# mSAS_BNC_fanout.net
KiCad netlist of a schematic drawn in Altium Designer
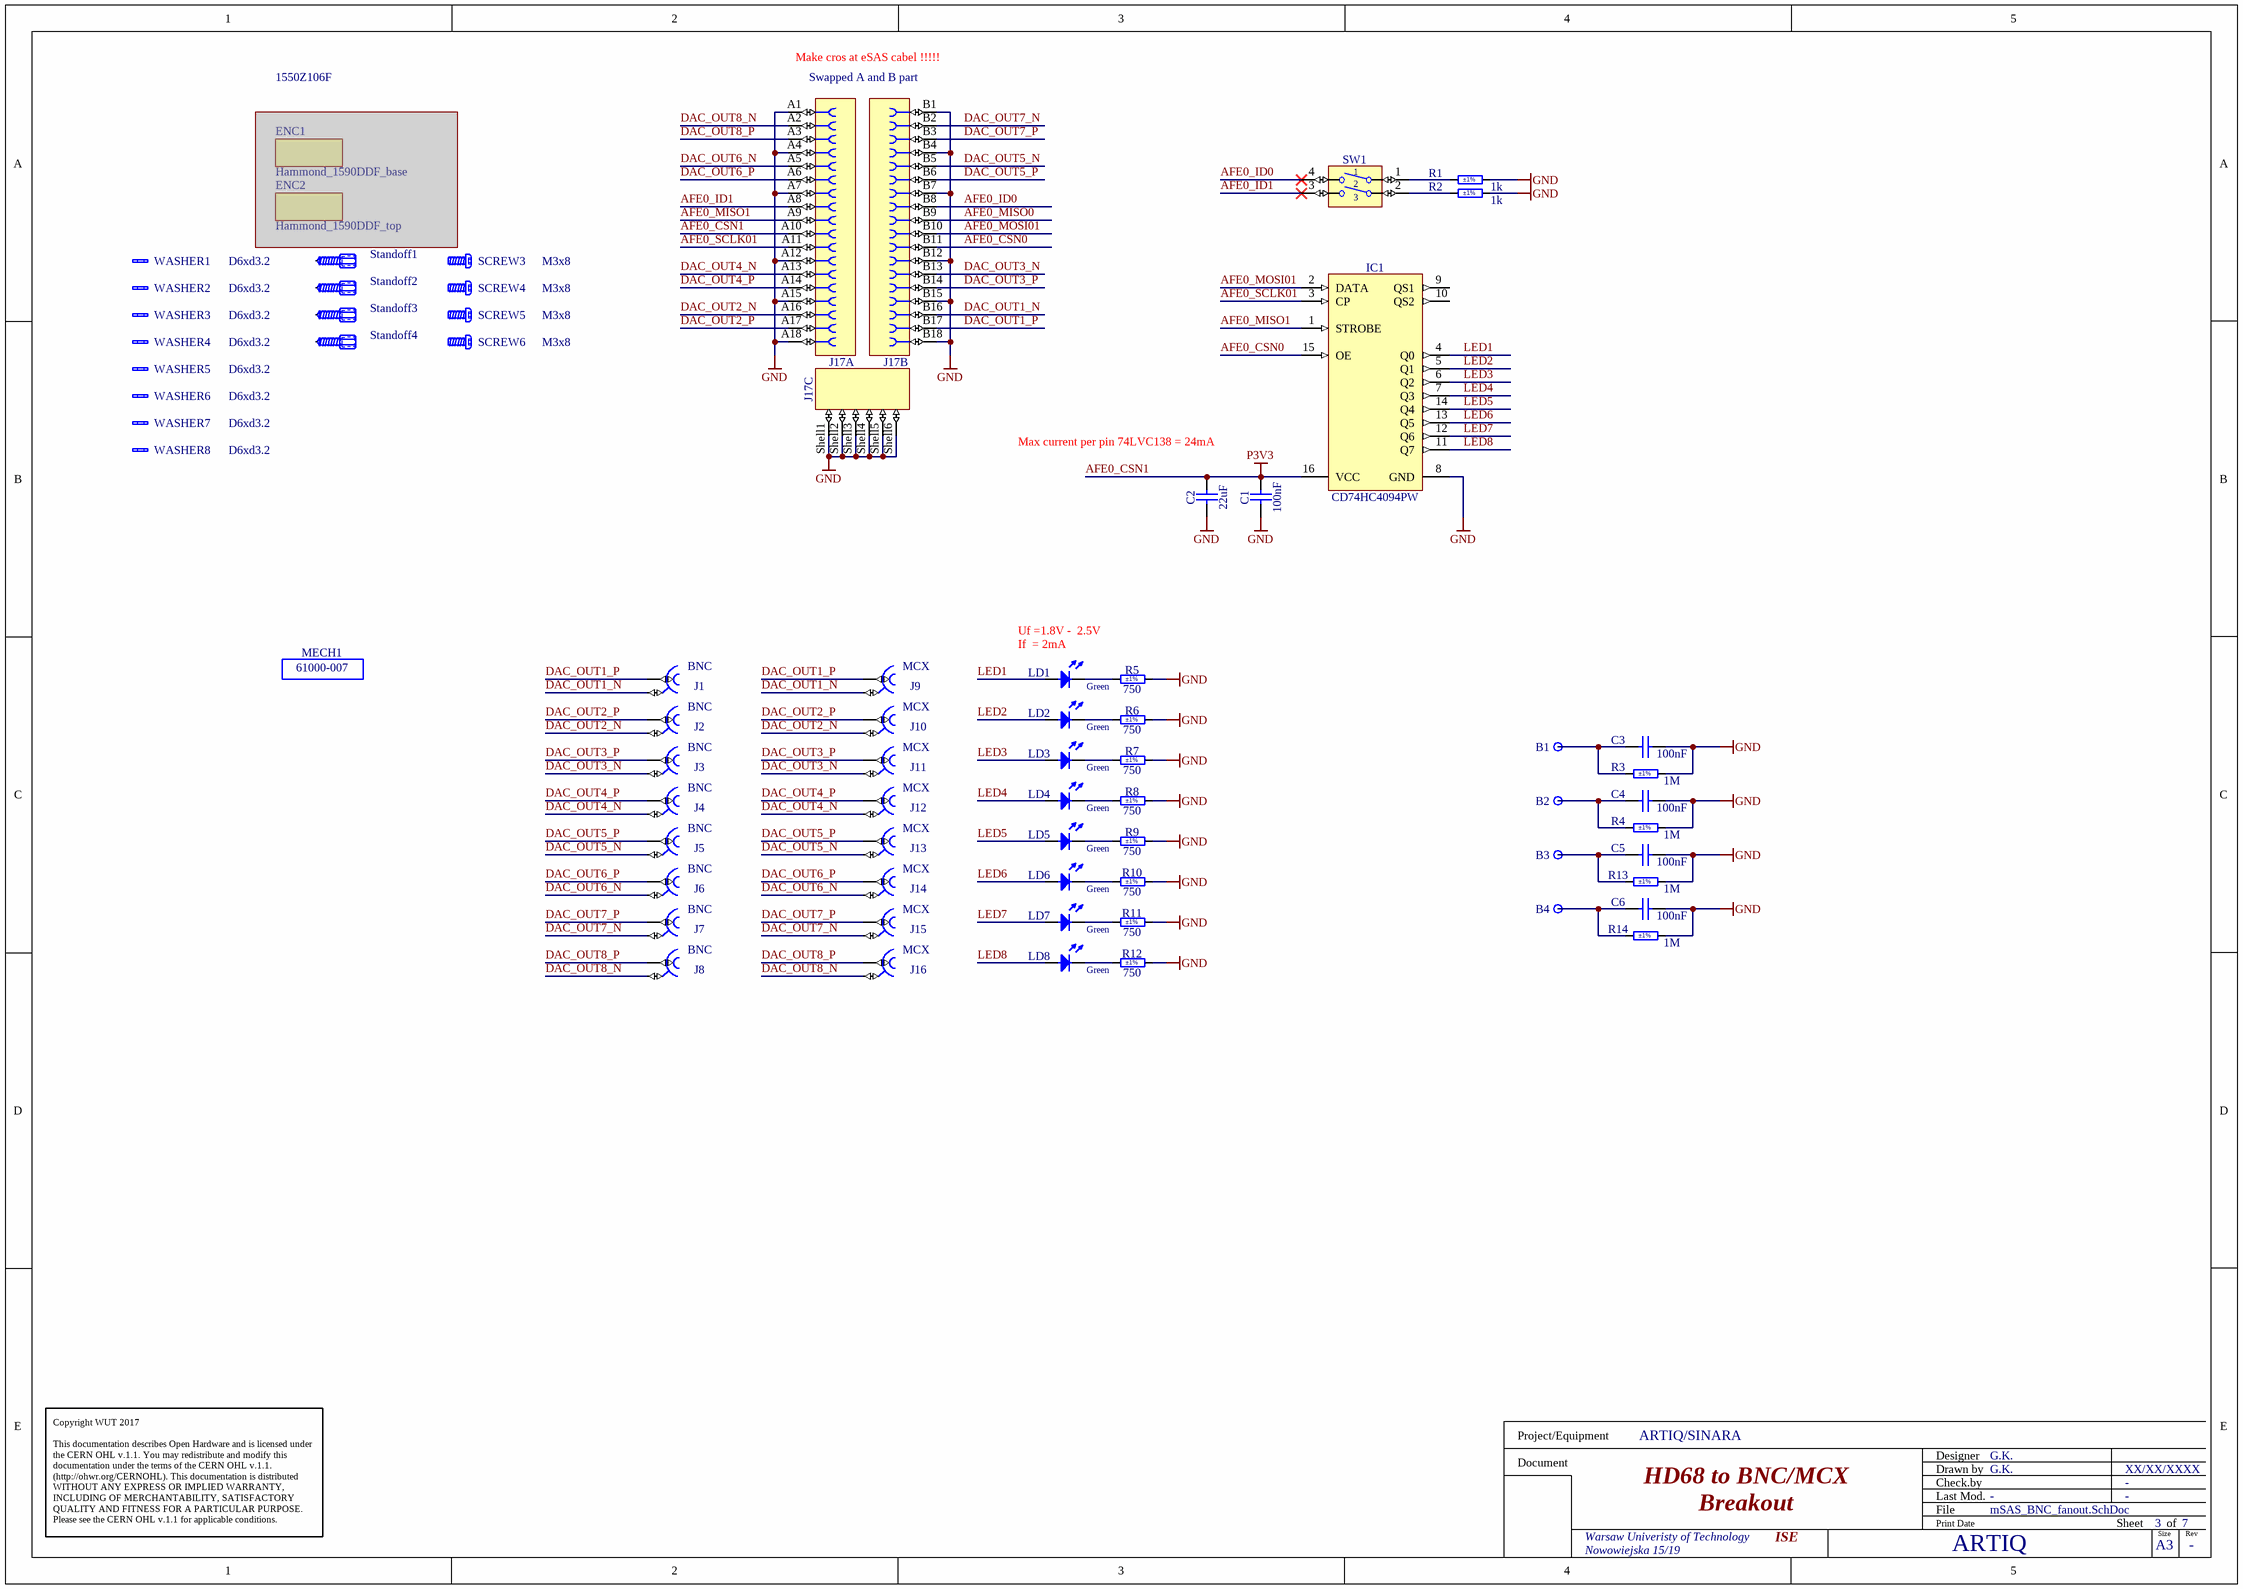
[diagram p0: mSAS_BNC_fanout.SchDoc]

(export (version "E")
  (design (tool "Eeschema 10.0.6"))
  (components
    (comp (ref "B1")
      (value "Plated Hole")
      (footprint "MTG270_500")
      (description "Single Terminal Socket")
      (fields (field (name "PART NUMBER") "PLATED_HOLE2.7_PAD5.0") (field (name "AUTHOR") "CERN DEM JMW"))
      (libsource (lib "Eletro-mechanical") (part "Single Terminal Socket"))
    )
    (comp (ref "B2")
      (value "Plated Hole")
      (footprint "MTG270_500")
      (description "Single Terminal Socket")
      (fields (field (name "PART NUMBER") "PLATED_HOLE2.7_PAD5.0") (field (name "AUTHOR") "CERN DEM JMW"))
      (libsource (lib "Eletro-mechanical") (part "Single Terminal Socket"))
    )
    (comp (ref "B3")
      (value "Plated Hole")
      (footprint "MTG270_500")
      (description "Single Terminal Socket")
      (fields (field (name "PART NUMBER") "PLATED_HOLE2.7_PAD5.0") (field (name "AUTHOR") "CERN DEM JMW"))
      (libsource (lib "Eletro-mechanical") (part "Single Terminal Socket"))
    )
    (comp (ref "B4")
      (value "Plated Hole")
      (footprint "MTG270_500")
      (description "Single Terminal Socket")
      (fields (field (name "PART NUMBER") "PLATED_HOLE2.7_PAD5.0") (field (name "AUTHOR") "CERN DEM JMW"))
      (libsource (lib "Eletro-mechanical") (part "Single Terminal Socket"))
    )
    (comp (ref "C1")
      (value "100nF")
      (footprint "CAPC1608X87N")
      (description "Non-polarised capacitor")
      (fields
        (field (name "PART NUMBER") "CC0603_100NF_50V_10%_X7R")
        (field (name "VOLTAGE") "50V")
        (field (name "AUTHOR") "CERN DEM JLC")
      )
      (libsource (lib "Capacitors") (part "Capacitor - non polarized"))
    )
    (comp (ref "C2")
      (value "22uF")
      (footprint "CAPC1608X90N")
      (description "Non-polarised capacitor")
      (fields
        (field (name "PART NUMBER") "CC0603_22UF_10V_20%_X5R")
        (field (name "VOLTAGE") "10V")
        (field (name "AUTHOR") "CERN DEM BC")
      )
      (libsource (lib "Capacitors") (part "Capacitor - non polarized"))
    )
    (comp (ref "C3")
      (value "100nF")
      (footprint "CAPC1608X90N")
      (description "Non-polarised capacitor")
      (fields
        (field (name "PART NUMBER") "CC0603_100NF_100V_10%_X7R")
        (field (name "VOLTAGE") "100V")
        (field (name "AUTHOR") "CERN DEM JLC")
      )
      (libsource (lib "Capacitors") (part "Capacitor - non polarized"))
    )
    (comp (ref "C4")
      (value "100nF")
      (footprint "CAPC1608X90N")
      (description "Non-polarised capacitor")
      (fields
        (field (name "PART NUMBER") "CC0603_100NF_100V_10%_X7R")
        (field (name "VOLTAGE") "100V")
        (field (name "AUTHOR") "CERN DEM JLC")
      )
      (libsource (lib "Capacitors") (part "Capacitor - non polarized"))
    )
    (comp (ref "C5")
      (value "100nF")
      (footprint "CAPC1608X90N")
      (description "Non-polarised capacitor")
      (fields
        (field (name "PART NUMBER") "CC0603_100NF_100V_10%_X7R")
        (field (name "VOLTAGE") "100V")
        (field (name "AUTHOR") "CERN DEM JLC")
      )
      (libsource (lib "Capacitors") (part "Capacitor - non polarized"))
    )
    (comp (ref "C6")
      (value "100nF")
      (footprint "CAPC1608X90N")
      (description "Non-polarised capacitor")
      (fields
        (field (name "PART NUMBER") "CC0603_100NF_100V_10%_X7R")
        (field (name "VOLTAGE") "100V")
        (field (name "AUTHOR") "CERN DEM JLC")
      )
      (libsource (lib "Capacitors") (part "Capacitor - non polarized"))
    )
    (comp (ref "ENC1")
      (value "Hammond_1590DDF_base")
      (footprint "1590DDF_base")
      (description "Hammond 1590DDF enclosure base part")
      (libsource (lib "Mechanical") (part "Hammond_1590DDF_base"))
    )
    (comp (ref "ENC2")
      (value "Hammond_1590DDF_top")
      (footprint "1590D-DD-E_LID_custom")
      (description "Hammond 1590DDF enclosure lid with custom cutouts")
      (libsource (lib "Mechanical") (part "Hammond_1590DDF_top_custom"))
    )
    (comp (ref "IC1")
      (value "CD74HC4094PW")
      (footprint "SOP65P640X120-16N")
      (description "High−Speed CMOS Logic, 8−Stage Shift and Store Bus Register, Three−State")
      (fields (field (name "MANUFACTURER") "TEXAS INSTRUMENTS") (field (name "AUTHOR") "CERN DEM MR"))
      (libsource (lib "ICs And Semiconductors") (part "744094"))
    )
    (comp (ref "J1")
      (value "BNC")
      (footprint "TYCO_5-1634506-1")
      (fields
        (field (name "PART NUMBER") "TYCO_5-1634506-1")
        (field (name "MANUFACTURER") "TYCO ELECTRONICS")
        (field (name "MANUFACTURER PART NUMBER") "5-1634506-1")
        (field (name "AUTHOR") "CERN DEM JLC")
      )
      (libsource (lib "Connectors") (part "Coax_1Female_1Shield"))
    )
    (comp (ref "J2")
      (value "BNC")
      (footprint "TYCO_5-1634506-1")
      (fields
        (field (name "PART NUMBER") "TYCO_5-1634506-1")
        (field (name "MANUFACTURER") "TYCO ELECTRONICS")
        (field (name "MANUFACTURER PART NUMBER") "5-1634506-1")
        (field (name "AUTHOR") "CERN DEM JLC")
      )
      (libsource (lib "Connectors") (part "Coax_1Female_1Shield"))
    )
    (comp (ref "J3")
      (value "BNC")
      (footprint "TYCO_5-1634506-1")
      (fields
        (field (name "PART NUMBER") "TYCO_5-1634506-1")
        (field (name "MANUFACTURER") "TYCO ELECTRONICS")
        (field (name "MANUFACTURER PART NUMBER") "5-1634506-1")
        (field (name "AUTHOR") "CERN DEM JLC")
      )
      (libsource (lib "Connectors") (part "Coax_1Female_1Shield"))
    )
    (comp (ref "J4")
      (value "BNC")
      (footprint "TYCO_5-1634506-1")
      (fields
        (field (name "PART NUMBER") "TYCO_5-1634506-1")
        (field (name "MANUFACTURER") "TYCO ELECTRONICS")
        (field (name "MANUFACTURER PART NUMBER") "5-1634506-1")
        (field (name "AUTHOR") "CERN DEM JLC")
      )
      (libsource (lib "Connectors") (part "Coax_1Female_1Shield"))
    )
    (comp (ref "J5")
      (value "BNC")
      (footprint "TYCO_5-1634506-1")
      (fields
        (field (name "PART NUMBER") "TYCO_5-1634506-1")
        (field (name "MANUFACTURER") "TYCO ELECTRONICS")
        (field (name "MANUFACTURER PART NUMBER") "5-1634506-1")
        (field (name "AUTHOR") "CERN DEM JLC")
      )
      (libsource (lib "Connectors") (part "Coax_1Female_1Shield"))
    )
    (comp (ref "J6")
      (value "BNC")
      (footprint "TYCO_5-1634506-1")
      (fields
        (field (name "PART NUMBER") "TYCO_5-1634506-1")
        (field (name "MANUFACTURER") "TYCO ELECTRONICS")
        (field (name "MANUFACTURER PART NUMBER") "5-1634506-1")
        (field (name "AUTHOR") "CERN DEM JLC")
      )
      (libsource (lib "Connectors") (part "Coax_1Female_1Shield"))
    )
    (comp (ref "J7")
      (value "BNC")
      (footprint "TYCO_5-1634506-1")
      (fields
        (field (name "PART NUMBER") "TYCO_5-1634506-1")
        (field (name "MANUFACTURER") "TYCO ELECTRONICS")
        (field (name "MANUFACTURER PART NUMBER") "5-1634506-1")
        (field (name "AUTHOR") "CERN DEM JLC")
      )
      (libsource (lib "Connectors") (part "Coax_1Female_1Shield"))
    )
    (comp (ref "J8")
      (value "BNC")
      (footprint "TYCO_5-1634506-1")
      (fields
        (field (name "PART NUMBER") "TYCO_5-1634506-1")
        (field (name "MANUFACTURER") "TYCO ELECTRONICS")
        (field (name "MANUFACTURER PART NUMBER") "5-1634506-1")
        (field (name "AUTHOR") "CERN DEM JLC")
      )
      (libsource (lib "Connectors") (part "Coax_1Female_1Shield"))
    )
    (comp (ref "J9")
      (value "MCX")
      (footprint "AMPHENOL_919-109J-51PX")
      (fields
        (field (name "PART NUMBER") "AMPHENOL_919-109J-51PX")
        (field (name "MANUFACTURER") "AMPHENOL")
        (field (name "MANUFACTURER PART NUMBER") "919-109J-51PX (MCX6251B1-3GT30G-50)")
        (field (name "AUTHOR") "CERN DEM BC")
      )
      (libsource (lib "Connectors") (part "Coax_1Female_1Shield"))
    )
    (comp (ref "J10")
      (value "MCX")
      (footprint "AMPHENOL_919-109J-51PX")
      (fields
        (field (name "PART NUMBER") "AMPHENOL_919-109J-51PX")
        (field (name "MANUFACTURER") "AMPHENOL")
        (field (name "MANUFACTURER PART NUMBER") "919-109J-51PX (MCX6251B1-3GT30G-50)")
        (field (name "AUTHOR") "CERN DEM BC")
      )
      (libsource (lib "Connectors") (part "Coax_1Female_1Shield"))
    )
    (comp (ref "J11")
      (value "MCX")
      (footprint "AMPHENOL_919-109J-51PX")
      (fields
        (field (name "PART NUMBER") "AMPHENOL_919-109J-51PX")
        (field (name "MANUFACTURER") "AMPHENOL")
        (field (name "MANUFACTURER PART NUMBER") "919-109J-51PX (MCX6251B1-3GT30G-50)")
        (field (name "AUTHOR") "CERN DEM BC")
      )
      (libsource (lib "Connectors") (part "Coax_1Female_1Shield"))
    )
    (comp (ref "J12")
      (value "MCX")
      (footprint "AMPHENOL_919-109J-51PX")
      (fields
        (field (name "PART NUMBER") "AMPHENOL_919-109J-51PX")
        (field (name "MANUFACTURER") "AMPHENOL")
        (field (name "MANUFACTURER PART NUMBER") "919-109J-51PX (MCX6251B1-3GT30G-50)")
        (field (name "AUTHOR") "CERN DEM BC")
      )
      (libsource (lib "Connectors") (part "Coax_1Female_1Shield"))
    )
    (comp (ref "J13")
      (value "MCX")
      (footprint "AMPHENOL_919-109J-51PX")
      (fields
        (field (name "PART NUMBER") "AMPHENOL_919-109J-51PX")
        (field (name "MANUFACTURER") "AMPHENOL")
        (field (name "MANUFACTURER PART NUMBER") "919-109J-51PX (MCX6251B1-3GT30G-50)")
        (field (name "AUTHOR") "CERN DEM BC")
      )
      (libsource (lib "Connectors") (part "Coax_1Female_1Shield"))
    )
    (comp (ref "J14")
      (value "MCX")
      (footprint "AMPHENOL_919-109J-51PX")
      (fields
        (field (name "PART NUMBER") "AMPHENOL_919-109J-51PX")
        (field (name "MANUFACTURER") "AMPHENOL")
        (field (name "MANUFACTURER PART NUMBER") "919-109J-51PX (MCX6251B1-3GT30G-50)")
        (field (name "AUTHOR") "CERN DEM BC")
      )
      (libsource (lib "Connectors") (part "Coax_1Female_1Shield"))
    )
    (comp (ref "J15")
      (value "MCX")
      (footprint "AMPHENOL_919-109J-51PX")
      (fields
        (field (name "PART NUMBER") "AMPHENOL_919-109J-51PX")
        (field (name "MANUFACTURER") "AMPHENOL")
        (field (name "MANUFACTURER PART NUMBER") "919-109J-51PX (MCX6251B1-3GT30G-50)")
        (field (name "AUTHOR") "CERN DEM BC")
      )
      (libsource (lib "Connectors") (part "Coax_1Female_1Shield"))
    )
    (comp (ref "J16")
      (value "MCX")
      (footprint "AMPHENOL_919-109J-51PX")
      (fields
        (field (name "PART NUMBER") "AMPHENOL_919-109J-51PX")
        (field (name "MANUFACTURER") "AMPHENOL")
        (field (name "MANUFACTURER PART NUMBER") "919-109J-51PX (MCX6251B1-3GT30G-50)")
        (field (name "AUTHOR") "CERN DEM BC")
      )
      (libsource (lib "Connectors") (part "Coax_1Female_1Shield"))
    )
    (comp (ref "J17")
      (value "iPass™")
      (footprint "MOLEX_75783-0107")
      (fields
        (field (name "PART NUMBER") "MOLEX 75783-0107 / 75783-0136")
        (field (name "MANUFACTURER") "MOLEX")
        (field (name "MANUFACTURER PART NUMBER") "75783-0107 / 75783-0136")
        (field (name "AUTHOR") "CERN DEM JLC")
      )
      (libsource (lib "") (part "MOLEX_75783-0107_1"))
    )
    (comp (ref "LD1")
      (value "Green")
      (footprint "LED_KINGBRIGHT_KP-1608CGCK")
      (description "LED Green 1C 2A")
      (fields
        (field (name "PART NUMBER") "LED_KINGBRIGHT_KP-1608CGCK")
        (field (name "MANUFACTURER") "KINGBRIGHT")
        (field (name "AUTHOR") "CERN DEM HF")
      )
      (libsource (lib "ICs And Semiconductors") (part "LED Green 1C 2A"))
    )
    (comp (ref "LD2")
      (value "Green")
      (footprint "LED_KINGBRIGHT_KP-1608CGCK")
      (description "LED Green 1C 2A")
      (fields
        (field (name "PART NUMBER") "LED_KINGBRIGHT_KP-1608CGCK")
        (field (name "MANUFACTURER") "KINGBRIGHT")
        (field (name "AUTHOR") "CERN DEM HF")
      )
      (libsource (lib "ICs And Semiconductors") (part "LED Green 1C 2A"))
    )
    (comp (ref "LD3")
      (value "Green")
      (footprint "LED_KINGBRIGHT_KP-1608CGCK")
      (description "LED Green 1C 2A")
      (fields
        (field (name "PART NUMBER") "LED_KINGBRIGHT_KP-1608CGCK")
        (field (name "MANUFACTURER") "KINGBRIGHT")
        (field (name "AUTHOR") "CERN DEM HF")
      )
      (libsource (lib "ICs And Semiconductors") (part "LED Green 1C 2A"))
    )
    (comp (ref "LD4")
      (value "Green")
      (footprint "LED_KINGBRIGHT_KP-1608CGCK")
      (description "LED Green 1C 2A")
      (fields
        (field (name "PART NUMBER") "LED_KINGBRIGHT_KP-1608CGCK")
        (field (name "MANUFACTURER") "KINGBRIGHT")
        (field (name "AUTHOR") "CERN DEM HF")
      )
      (libsource (lib "ICs And Semiconductors") (part "LED Green 1C 2A"))
    )
    (comp (ref "LD5")
      (value "Green")
      (footprint "LED_KINGBRIGHT_KP-1608CGCK")
      (description "LED Green 1C 2A")
      (fields
        (field (name "PART NUMBER") "LED_KINGBRIGHT_KP-1608CGCK")
        (field (name "MANUFACTURER") "KINGBRIGHT")
        (field (name "AUTHOR") "CERN DEM HF")
      )
      (libsource (lib "ICs And Semiconductors") (part "LED Green 1C 2A"))
    )
    (comp (ref "LD6")
      (value "Green")
      (footprint "LED_KINGBRIGHT_KP-1608CGCK")
      (description "LED Green 1C 2A")
      (fields
        (field (name "PART NUMBER") "LED_KINGBRIGHT_KP-1608CGCK")
        (field (name "MANUFACTURER") "KINGBRIGHT")
        (field (name "AUTHOR") "CERN DEM HF")
      )
      (libsource (lib "ICs And Semiconductors") (part "LED Green 1C 2A"))
    )
    (comp (ref "LD7")
      (value "Green")
      (footprint "LED_KINGBRIGHT_KP-1608CGCK")
      (description "LED Green 1C 2A")
      (fields
        (field (name "PART NUMBER") "LED_KINGBRIGHT_KP-1608CGCK")
        (field (name "MANUFACTURER") "KINGBRIGHT")
        (field (name "AUTHOR") "CERN DEM HF")
      )
      (libsource (lib "ICs And Semiconductors") (part "LED Green 1C 2A"))
    )
    (comp (ref "LD8")
      (value "Green")
      (footprint "LED_KINGBRIGHT_KP-1608CGCK")
      (description "LED Green 1C 2A")
      (fields
        (field (name "PART NUMBER") "LED_KINGBRIGHT_KP-1608CGCK")
        (field (name "MANUFACTURER") "KINGBRIGHT")
        (field (name "AUTHOR") "CERN DEM HF")
      )
      (libsource (lib "ICs And Semiconductors") (part "LED Green 1C 2A"))
    )
    (comp (ref "MECH1")
      (value "61000-007")
      (footprint "GENERIC_MECH")
      (description "PCB Solder Side Cover, 3 U, 100 mm x 160 mm, 55°C Schroff insulating plate")
      (fields (field (name "MANUFACTURER") "Schroff") (field (name "AUTHOR") "GK"))
      (libsource (lib "Mechanical") (part "Generic_mechanical"))
    )
    (comp (ref "R1")
      (value "1k")
      (footprint "RESC1608X55N")
      (description "Resistor - 1%")
      (fields
        (field (name "TOLERANCE") "±1%")
        (field (name "PART NUMBER") "R0603_1K_1%_0.1W_100PPM")
        (field (name "POWER") "0.1W")
        (field (name "AUTHOR") "CERN DEM JLC")
      )
      (libsource (lib "Resistors") (part "Resistor - 1%"))
    )
    (comp (ref "R2")
      (value "1k")
      (footprint "RESC1608X55N")
      (description "Resistor - 1%")
      (fields
        (field (name "TOLERANCE") "±1%")
        (field (name "PART NUMBER") "R0603_1K_1%_0.1W_100PPM")
        (field (name "POWER") "0.1W")
        (field (name "AUTHOR") "CERN DEM JLC")
      )
      (libsource (lib "Resistors") (part "Resistor - 1%"))
    )
    (comp (ref "R3")
      (value "1M")
      (footprint "RESC1608X55N")
      (description "Resistor - 1%")
      (fields
        (field (name "TOLERANCE") "±1%")
        (field (name "PART NUMBER") "R0603_1M_1%_0.1W_100PPM")
        (field (name "POWER") "0.1W")
        (field (name "AUTHOR") "CERN DEM JLC")
      )
      (libsource (lib "Resistors") (part "Resistor - 1%"))
    )
    (comp (ref "R4")
      (value "1M")
      (footprint "RESC1608X55N")
      (description "Resistor - 1%")
      (fields
        (field (name "TOLERANCE") "±1%")
        (field (name "PART NUMBER") "R0603_1M_1%_0.1W_100PPM")
        (field (name "POWER") "0.1W")
        (field (name "AUTHOR") "CERN DEM JLC")
      )
      (libsource (lib "Resistors") (part "Resistor - 1%"))
    )
    (comp (ref "R5")
      (value "750")
      (footprint "RESC1608X55N")
      (description "Resistor - 1%")
      (fields
        (field (name "TOLERANCE") "±1%")
        (field (name "PART NUMBER") "R0603_750R_1%_0.1W_100PPM")
        (field (name "POWER") "0.1W")
        (field (name "AUTHOR") "CERN DEM JLC")
      )
      (libsource (lib "Resistors") (part "Resistor - 1%"))
    )
    (comp (ref "R6")
      (value "750")
      (footprint "RESC1608X55N")
      (description "Resistor - 1%")
      (fields
        (field (name "TOLERANCE") "±1%")
        (field (name "PART NUMBER") "R0603_750R_1%_0.1W_100PPM")
        (field (name "POWER") "0.1W")
        (field (name "AUTHOR") "CERN DEM JLC")
      )
      (libsource (lib "Resistors") (part "Resistor - 1%"))
    )
    (comp (ref "R7")
      (value "750")
      (footprint "RESC1608X55N")
      (description "Resistor - 1%")
      (fields
        (field (name "TOLERANCE") "±1%")
        (field (name "PART NUMBER") "R0603_750R_1%_0.1W_100PPM")
        (field (name "POWER") "0.1W")
        (field (name "AUTHOR") "CERN DEM JLC")
      )
      (libsource (lib "Resistors") (part "Resistor - 1%"))
    )
    (comp (ref "R8")
      (value "750")
      (footprint "RESC1608X55N")
      (description "Resistor - 1%")
      (fields
        (field (name "TOLERANCE") "±1%")
        (field (name "PART NUMBER") "R0603_750R_1%_0.1W_100PPM")
        (field (name "POWER") "0.1W")
        (field (name "AUTHOR") "CERN DEM JLC")
      )
      (libsource (lib "Resistors") (part "Resistor - 1%"))
    )
    (comp (ref "R9")
      (value "750")
      (footprint "RESC1608X55N")
      (description "Resistor - 1%")
      (fields
        (field (name "TOLERANCE") "±1%")
        (field (name "PART NUMBER") "R0603_750R_1%_0.1W_100PPM")
        (field (name "POWER") "0.1W")
        (field (name "AUTHOR") "CERN DEM JLC")
      )
      (libsource (lib "Resistors") (part "Resistor - 1%"))
    )
    (comp (ref "R10")
      (value "750")
      (footprint "RESC1608X55N")
      (description "Resistor - 1%")
      (fields
        (field (name "TOLERANCE") "±1%")
        (field (name "PART NUMBER") "R0603_750R_1%_0.1W_100PPM")
        (field (name "POWER") "0.1W")
        (field (name "AUTHOR") "CERN DEM JLC")
      )
      (libsource (lib "Resistors") (part "Resistor - 1%"))
    )
    (comp (ref "R11")
      (value "750")
      (footprint "RESC1608X55N")
      (description "Resistor - 1%")
      (fields
        (field (name "TOLERANCE") "±1%")
        (field (name "PART NUMBER") "R0603_750R_1%_0.1W_100PPM")
        (field (name "POWER") "0.1W")
        (field (name "AUTHOR") "CERN DEM JLC")
      )
      (libsource (lib "Resistors") (part "Resistor - 1%"))
    )
    (comp (ref "R12")
      (value "750")
      (footprint "RESC1608X55N")
      (description "Resistor - 1%")
      (fields
        (field (name "TOLERANCE") "±1%")
        (field (name "PART NUMBER") "R0603_750R_1%_0.1W_100PPM")
        (field (name "POWER") "0.1W")
        (field (name "AUTHOR") "CERN DEM JLC")
      )
      (libsource (lib "Resistors") (part "Resistor - 1%"))
    )
    (comp (ref "R13")
      (value "1M")
      (footprint "RESC1608X55N")
      (description "Resistor - 1%")
      (fields
        (field (name "TOLERANCE") "±1%")
        (field (name "PART NUMBER") "R0603_1M_1%_0.1W_100PPM")
        (field (name "POWER") "0.1W")
        (field (name "AUTHOR") "CERN DEM JLC")
      )
      (libsource (lib "Resistors") (part "Resistor - 1%"))
    )
    (comp (ref "R14")
      (value "1M")
      (footprint "RESC1608X55N")
      (description "Resistor - 1%")
      (fields
        (field (name "TOLERANCE") "±1%")
        (field (name "PART NUMBER") "R0603_1M_1%_0.1W_100PPM")
        (field (name "POWER") "0.1W")
        (field (name "AUTHOR") "CERN DEM JLC")
      )
      (libsource (lib "Resistors") (part "Resistor - 1%"))
    )
    (comp (ref "SCREW3")
      (value "M3x8")
      (footprint "BOSSARD_BN5687-3061606_h")
      (description "Screw")
      (fields
        (field (name "PART NUMBER") "BOSSARD_BN5687-3061606_h")
        (field (name "MANUFACTURER") "BOSSARD")
        (field (name "AUTHOR") "CERN DEM JLC")
      )
      (libsource (lib "Eletro-mechanical") (part "Screw"))
    )
    (comp (ref "SCREW4")
      (value "M3x8")
      (footprint "BOSSARD_BN5687-3061606_h")
      (description "Screw")
      (fields
        (field (name "PART NUMBER") "BOSSARD_BN5687-3061606_h")
        (field (name "MANUFACTURER") "BOSSARD")
        (field (name "AUTHOR") "CERN DEM JLC")
      )
      (libsource (lib "Eletro-mechanical") (part "Screw"))
    )
    (comp (ref "SCREW5")
      (value "M3x8")
      (footprint "BOSSARD_BN5687-3061606_h")
      (description "Screw")
      (fields
        (field (name "PART NUMBER") "BOSSARD_BN5687-3061606_h")
        (field (name "MANUFACTURER") "BOSSARD")
        (field (name "AUTHOR") "CERN DEM JLC")
      )
      (libsource (lib "Eletro-mechanical") (part "Screw"))
    )
    (comp (ref "SCREW6")
      (value "M3x8")
      (footprint "BOSSARD_BN5687-3061606_h")
      (description "Screw")
      (fields
        (field (name "PART NUMBER") "BOSSARD_BN5687-3061606_h")
        (field (name "MANUFACTURER") "BOSSARD")
        (field (name "AUTHOR") "CERN DEM JLC")
      )
      (libsource (lib "Eletro-mechanical") (part "Screw"))
    )
    (comp (ref "Standoff1")
      (value "~")
      (footprint "ETTINGER_005.13.103")
      (description "Standoff Male-Female")
      (fields
        (field (name "PART NUMBER") "ETTINGER_005.13.103")
        (field (name "MANUFACTURER") "ETTINGER")
        (field (name "AUTHOR") "CERN DEM HF")
      )
      (libsource (lib "Eletro-mechanical") (part "Standoff Male-Female"))
    )
    (comp (ref "Standoff2")
      (value "~")
      (footprint "ETTINGER_005.13.103")
      (description "Standoff Male-Female")
      (fields
        (field (name "PART NUMBER") "ETTINGER_005.13.103")
        (field (name "MANUFACTURER") "ETTINGER")
        (field (name "AUTHOR") "CERN DEM HF")
      )
      (libsource (lib "Eletro-mechanical") (part "Standoff Male-Female"))
    )
    (comp (ref "Standoff3")
      (value "~")
      (footprint "ETTINGER_005.13.103")
      (description "Standoff Male-Female")
      (fields
        (field (name "PART NUMBER") "ETTINGER_005.13.103")
        (field (name "MANUFACTURER") "ETTINGER")
        (field (name "AUTHOR") "CERN DEM HF")
      )
      (libsource (lib "Eletro-mechanical") (part "Standoff Male-Female"))
    )
    (comp (ref "Standoff4")
      (value "~")
      (footprint "ETTINGER_005.13.103")
      (description "Standoff Male-Female")
      (fields
        (field (name "PART NUMBER") "ETTINGER_005.13.103")
        (field (name "MANUFACTURER") "ETTINGER")
        (field (name "AUTHOR") "CERN DEM HF")
      )
      (libsource (lib "Eletro-mechanical") (part "Standoff Male-Female"))
    )
    (comp (ref "SW1")
      (value "Switch")
      (footprint "SW_OMRON_A6DR-2101")
      (description "2 Ways SPST DIP Switch")
      (fields (field (name "PART NUMBER") "SW_OMRON_A6FR-2101") (field (name "MANUFACTURER") "OMRON"))
      (libsource (lib "eSAS_BNC_fanout") (part "SW_OMRON_A6DR-2101"))
    )
    (comp (ref "WASHER1")
      (value "D6xd3.2")
      (footprint "BOSSARD_BN83728-8243964_v")
      (description "Washer")
      (fields
        (field (name "PART NUMBER") "BOSSARD_BN83728-8243964_v")
        (field (name "MANUFACTURER") "BOSSARD")
        (field (name "AUTHOR") "CERN DEM JLC")
      )
      (libsource (lib "Eletro-mechanical") (part "Washer"))
    )
    (comp (ref "WASHER2")
      (value "D6xd3.2")
      (footprint "BOSSARD_BN83728-8243964_v")
      (description "Washer")
      (fields
        (field (name "PART NUMBER") "BOSSARD_BN83728-8243964_v")
        (field (name "MANUFACTURER") "BOSSARD")
        (field (name "AUTHOR") "CERN DEM JLC")
      )
      (libsource (lib "Eletro-mechanical") (part "Washer"))
    )
    (comp (ref "WASHER3")
      (value "D6xd3.2")
      (footprint "BOSSARD_BN83728-8243964_v")
      (description "Washer")
      (fields
        (field (name "PART NUMBER") "BOSSARD_BN83728-8243964_v")
        (field (name "MANUFACTURER") "BOSSARD")
        (field (name "AUTHOR") "CERN DEM JLC")
      )
      (libsource (lib "Eletro-mechanical") (part "Washer"))
    )
    (comp (ref "WASHER4")
      (value "D6xd3.2")
      (footprint "BOSSARD_BN83728-8243964_v")
      (description "Washer")
      (fields
        (field (name "PART NUMBER") "BOSSARD_BN83728-8243964_v")
        (field (name "MANUFACTURER") "BOSSARD")
        (field (name "AUTHOR") "CERN DEM JLC")
      )
      (libsource (lib "Eletro-mechanical") (part "Washer"))
    )
    (comp (ref "WASHER5")
      (value "D6xd3.2")
      (footprint "BOSSARD_BN83728-8243964_v")
      (description "Washer")
      (fields
        (field (name "PART NUMBER") "BOSSARD_BN83728-8243964_v")
        (field (name "MANUFACTURER") "BOSSARD")
        (field (name "AUTHOR") "CERN DEM JLC")
      )
      (libsource (lib "Eletro-mechanical") (part "Washer"))
    )
    (comp (ref "WASHER6")
      (value "D6xd3.2")
      (footprint "BOSSARD_BN83728-8243964_v")
      (description "Washer")
      (fields
        (field (name "PART NUMBER") "BOSSARD_BN83728-8243964_v")
        (field (name "MANUFACTURER") "BOSSARD")
        (field (name "AUTHOR") "CERN DEM JLC")
      )
      (libsource (lib "Eletro-mechanical") (part "Washer"))
    )
    (comp (ref "WASHER7")
      (value "D6xd3.2")
      (footprint "BOSSARD_BN83728-8243964_v")
      (description "Washer")
      (fields
        (field (name "PART NUMBER") "BOSSARD_BN83728-8243964_v")
        (field (name "MANUFACTURER") "BOSSARD")
        (field (name "AUTHOR") "CERN DEM JLC")
      )
      (libsource (lib "Eletro-mechanical") (part "Washer"))
    )
    (comp (ref "WASHER8")
      (value "D6xd3.2")
      (footprint "BOSSARD_BN83728-8243964_v")
      (description "Washer")
      (fields
        (field (name "PART NUMBER") "BOSSARD_BN83728-8243964_v")
        (field (name "MANUFACTURER") "BOSSARD")
        (field (name "AUTHOR") "CERN DEM JLC")
      )
      (libsource (lib "Eletro-mechanical") (part "Washer"))
    )
  )
  (nets
    (net (code "1") (name "/AFE0_CSN0") (class "Default")
      (node (ref "IC1") (pin "15") (pinfunction "OE_15") (pintype "input"))
      (node (ref "J17") (pin "B11") (pinfunction "B11_B11") (pintype "bidirectional"))
    )
    (net (code "2") (name "/AFE0_ID0") (class "Default")
      (node (ref "J17") (pin "B8") (pinfunction "B8_B8") (pintype "bidirectional"))
      (node (ref "SW1") (pin "4") (pinfunction "4_4") (pintype "bidirectional"))
    )
    (net (code "3") (name "/AFE0_ID1") (class "Default")
      (node (ref "J17") (pin "A8") (pinfunction "A8_A8") (pintype "bidirectional"))
      (node (ref "SW1") (pin "3") (pinfunction "3_3") (pintype "bidirectional"))
    )
    (net (code "4") (name "/AFE0_MISO0") (class "Default")
      (node (ref "J17") (pin "B9") (pinfunction "B9_B9") (pintype "bidirectional"))
    )
    (net (code "5") (name "/AFE0_MISO1") (class "Default")
      (node (ref "IC1") (pin "1") (pinfunction "STROBE_1") (pintype "input"))
      (node (ref "J17") (pin "A9") (pinfunction "A9_A9") (pintype "bidirectional"))
    )
    (net (code "6") (name "/AFE0_MOSI01") (class "Default")
      (node (ref "IC1") (pin "2") (pinfunction "DATA_2") (pintype "input"))
      (node (ref "J17") (pin "B10") (pinfunction "B10_B10") (pintype "bidirectional"))
    )
    (net (code "7") (name "/AFE0_SCLK01") (class "Default")
      (node (ref "IC1") (pin "3") (pinfunction "CP_3") (pintype "input"))
      (node (ref "J17") (pin "A11") (pinfunction "A11_A11") (pintype "bidirectional"))
    )
    (net (code "8") (name "/DAC_OUT1_N") (class "Default")
      (node (ref "J1") (pin "2") (pinfunction "2_2") (pintype "bidirectional"))
      (node (ref "J17") (pin "B16") (pinfunction "B16_B16") (pintype "bidirectional"))
      (node (ref "J9") (pin "2") (pinfunction "2_2") (pintype "bidirectional"))
    )
    (net (code "9") (name "/DAC_OUT1_P") (class "Default")
      (node (ref "J1") (pin "1") (pinfunction "1_1") (pintype "bidirectional"))
      (node (ref "J17") (pin "B17") (pinfunction "B17_B17") (pintype "bidirectional"))
      (node (ref "J9") (pin "1") (pinfunction "1_1") (pintype "bidirectional"))
    )
    (net (code "10") (name "/DAC_OUT2_N") (class "Default")
      (node (ref "J10") (pin "2") (pinfunction "2_2") (pintype "bidirectional"))
      (node (ref "J17") (pin "A16") (pinfunction "A16_A16") (pintype "bidirectional"))
      (node (ref "J2") (pin "2") (pinfunction "2_2") (pintype "bidirectional"))
    )
    (net (code "11") (name "/DAC_OUT2_P") (class "Default")
      (node (ref "J10") (pin "1") (pinfunction "1_1") (pintype "bidirectional"))
      (node (ref "J17") (pin "A17") (pinfunction "A17_A17") (pintype "bidirectional"))
      (node (ref "J2") (pin "1") (pinfunction "1_1") (pintype "bidirectional"))
    )
    (net (code "12") (name "/DAC_OUT3_N") (class "Default")
      (node (ref "J11") (pin "2") (pinfunction "2_2") (pintype "bidirectional"))
      (node (ref "J17") (pin "B13") (pinfunction "B13_B13") (pintype "bidirectional"))
      (node (ref "J3") (pin "2") (pinfunction "2_2") (pintype "bidirectional"))
    )
    (net (code "13") (name "/DAC_OUT3_P") (class "Default")
      (node (ref "J11") (pin "1") (pinfunction "1_1") (pintype "bidirectional"))
      (node (ref "J17") (pin "B14") (pinfunction "B14_B14") (pintype "bidirectional"))
      (node (ref "J3") (pin "1") (pinfunction "1_1") (pintype "bidirectional"))
    )
    (net (code "14") (name "/DAC_OUT4_N") (class "Default")
      (node (ref "J12") (pin "2") (pinfunction "2_2") (pintype "bidirectional"))
      (node (ref "J17") (pin "A13") (pinfunction "A13_A13") (pintype "bidirectional"))
      (node (ref "J4") (pin "2") (pinfunction "2_2") (pintype "bidirectional"))
    )
    (net (code "15") (name "/DAC_OUT4_P") (class "Default")
      (node (ref "J12") (pin "1") (pinfunction "1_1") (pintype "bidirectional"))
      (node (ref "J17") (pin "A14") (pinfunction "A14_A14") (pintype "bidirectional"))
      (node (ref "J4") (pin "1") (pinfunction "1_1") (pintype "bidirectional"))
    )
    (net (code "16") (name "/DAC_OUT5_N") (class "Default")
      (node (ref "J13") (pin "2") (pinfunction "2_2") (pintype "bidirectional"))
      (node (ref "J17") (pin "B5") (pinfunction "B5_B5") (pintype "bidirectional"))
      (node (ref "J5") (pin "2") (pinfunction "2_2") (pintype "bidirectional"))
    )
    (net (code "17") (name "/DAC_OUT5_P") (class "Default")
      (node (ref "J13") (pin "1") (pinfunction "1_1") (pintype "bidirectional"))
      (node (ref "J17") (pin "B6") (pinfunction "B6_B6") (pintype "bidirectional"))
      (node (ref "J5") (pin "1") (pinfunction "1_1") (pintype "bidirectional"))
    )
    (net (code "18") (name "/DAC_OUT6_N") (class "Default")
      (node (ref "J14") (pin "2") (pinfunction "2_2") (pintype "bidirectional"))
      (node (ref "J17") (pin "A5") (pinfunction "A5_A5") (pintype "bidirectional"))
      (node (ref "J6") (pin "2") (pinfunction "2_2") (pintype "bidirectional"))
    )
    (net (code "19") (name "/DAC_OUT6_P") (class "Default")
      (node (ref "J14") (pin "1") (pinfunction "1_1") (pintype "bidirectional"))
      (node (ref "J17") (pin "A6") (pinfunction "A6_A6") (pintype "bidirectional"))
      (node (ref "J6") (pin "1") (pinfunction "1_1") (pintype "bidirectional"))
    )
    (net (code "20") (name "/DAC_OUT7_N") (class "Default")
      (node (ref "J15") (pin "2") (pinfunction "2_2") (pintype "bidirectional"))
      (node (ref "J17") (pin "B2") (pinfunction "B2_B2") (pintype "bidirectional"))
      (node (ref "J7") (pin "2") (pinfunction "2_2") (pintype "bidirectional"))
    )
    (net (code "21") (name "/DAC_OUT7_P") (class "Default")
      (node (ref "J15") (pin "1") (pinfunction "1_1") (pintype "bidirectional"))
      (node (ref "J17") (pin "B3") (pinfunction "B3_B3") (pintype "bidirectional"))
      (node (ref "J7") (pin "1") (pinfunction "1_1") (pintype "bidirectional"))
    )
    (net (code "22") (name "/DAC_OUT8_N") (class "Default")
      (node (ref "J16") (pin "2") (pinfunction "2_2") (pintype "bidirectional"))
      (node (ref "J17") (pin "A2") (pinfunction "A2_A2") (pintype "bidirectional"))
      (node (ref "J8") (pin "2") (pinfunction "2_2") (pintype "bidirectional"))
    )
    (net (code "23") (name "/DAC_OUT8_P") (class "Default")
      (node (ref "J16") (pin "1") (pinfunction "1_1") (pintype "bidirectional"))
      (node (ref "J17") (pin "A3") (pinfunction "A3_A3") (pintype "bidirectional"))
      (node (ref "J8") (pin "1") (pinfunction "1_1") (pintype "bidirectional"))
    )
    (net (code "24") (name "/LED1") (class "Default")
      (node (ref "IC1") (pin "4") (pinfunction "Q0_4") (pintype "output"))
      (node (ref "LD1") (pin "2") (pinfunction "A_2") (pintype "passive"))
    )
    (net (code "25") (name "/LED2") (class "Default")
      (node (ref "IC1") (pin "5") (pinfunction "Q1_5") (pintype "output"))
      (node (ref "LD2") (pin "2") (pinfunction "A_2") (pintype "passive"))
    )
    (net (code "26") (name "/LED3") (class "Default")
      (node (ref "IC1") (pin "6") (pinfunction "Q2_6") (pintype "output"))
      (node (ref "LD3") (pin "2") (pinfunction "A_2") (pintype "passive"))
    )
    (net (code "27") (name "/LED4") (class "Default")
      (node (ref "IC1") (pin "7") (pinfunction "Q3_7") (pintype "output"))
      (node (ref "LD4") (pin "2") (pinfunction "A_2") (pintype "passive"))
    )
    (net (code "28") (name "/LED5") (class "Default")
      (node (ref "IC1") (pin "14") (pinfunction "Q4_14") (pintype "output"))
      (node (ref "LD5") (pin "2") (pinfunction "A_2") (pintype "passive"))
    )
    (net (code "29") (name "/LED6") (class "Default")
      (node (ref "IC1") (pin "13") (pinfunction "Q5_13") (pintype "output"))
      (node (ref "LD6") (pin "2") (pinfunction "A_2") (pintype "passive"))
    )
    (net (code "30") (name "/LED7") (class "Default")
      (node (ref "IC1") (pin "12") (pinfunction "Q6_12") (pintype "output"))
      (node (ref "LD7") (pin "2") (pinfunction "A_2") (pintype "passive"))
    )
    (net (code "31") (name "/LED8") (class "Default")
      (node (ref "IC1") (pin "11") (pinfunction "Q7_11") (pintype "output"))
      (node (ref "LD8") (pin "2") (pinfunction "A_2") (pintype "passive"))
    )
    (net (code "32") (name "GND") (class "Default")
      (node (ref "C1") (pin "1") (pinfunction "1_1") (pintype "passive"))
      (node (ref "C2") (pin "1") (pinfunction "1_1") (pintype "passive"))
      (node (ref "C3") (pin "2") (pinfunction "2_2") (pintype "passive"))
      (node (ref "C4") (pin "2") (pinfunction "2_2") (pintype "passive"))
      (node (ref "C5") (pin "2") (pinfunction "2_2") (pintype "passive"))
      (node (ref "C6") (pin "2") (pinfunction "2_2") (pintype "passive"))
      (node (ref "IC1") (pin "8") (pinfunction "GND_8") (pintype "power_in"))
      (node (ref "J17") (pin "A1") (pinfunction "A1_A1") (pintype "bidirectional"))
      (node (ref "J17") (pin "A12") (pinfunction "A12_A12") (pintype "bidirectional"))
      (node (ref "J17") (pin "A15") (pinfunction "A15_A15") (pintype "bidirectional"))
      (node (ref "J17") (pin "A18") (pinfunction "A18_A18") (pintype "bidirectional"))
      (node (ref "J17") (pin "A4") (pinfunction "A4_A4") (pintype "bidirectional"))
      (node (ref "J17") (pin "A7") (pinfunction "A7_A7") (pintype "bidirectional"))
      (node (ref "J17") (pin "B1") (pinfunction "B1_B1") (pintype "bidirectional"))
      (node (ref "J17") (pin "B12") (pinfunction "B12_B12") (pintype "bidirectional"))
      (node (ref "J17") (pin "B15") (pinfunction "B15_B15") (pintype "bidirectional"))
      (node (ref "J17") (pin "B18") (pinfunction "B18_B18") (pintype "bidirectional"))
      (node (ref "J17") (pin "B4") (pinfunction "B4_B4") (pintype "bidirectional"))
      (node (ref "J17") (pin "B7") (pinfunction "B7_B7") (pintype "bidirectional"))
      (node (ref "J17") (pin "Shell1") (pinfunction "Shell1_Shell1") (pintype "bidirectional"))
      (node (ref "J17") (pin "Shell2") (pinfunction "Shell2_Shell2") (pintype "bidirectional"))
      (node (ref "J17") (pin "Shell3") (pinfunction "Shell3_Shell3") (pintype "bidirectional"))
      (node (ref "J17") (pin "Shell4") (pinfunction "Shell4_Shell4") (pintype "bidirectional"))
      (node (ref "J17") (pin "Shell5") (pinfunction "Shell5_Shell5") (pintype "bidirectional"))
      (node (ref "J17") (pin "Shell6") (pinfunction "Shell6_Shell6") (pintype "bidirectional"))
      (node (ref "R1") (pin "2") (pinfunction "2_2") (pintype "passive"))
      (node (ref "R10") (pin "2") (pinfunction "2_2") (pintype "passive"))
      (node (ref "R11") (pin "2") (pinfunction "2_2") (pintype "passive"))
      (node (ref "R12") (pin "2") (pinfunction "2_2") (pintype "passive"))
      (node (ref "R13") (pin "2") (pinfunction "2_2") (pintype "passive"))
      (node (ref "R14") (pin "2") (pinfunction "2_2") (pintype "passive"))
      (node (ref "R2") (pin "2") (pinfunction "2_2") (pintype "passive"))
      (node (ref "R3") (pin "2") (pinfunction "2_2") (pintype "passive"))
      (node (ref "R4") (pin "2") (pinfunction "2_2") (pintype "passive"))
      (node (ref "R5") (pin "2") (pinfunction "2_2") (pintype "passive"))
      (node (ref "R6") (pin "2") (pinfunction "2_2") (pintype "passive"))
      (node (ref "R7") (pin "2") (pinfunction "2_2") (pintype "passive"))
      (node (ref "R8") (pin "2") (pinfunction "2_2") (pintype "passive"))
      (node (ref "R9") (pin "2") (pinfunction "2_2") (pintype "passive"))
    )
    (net (code "33") (name "Net-(B1-Pad1)") (class "Default")
      (node (ref "B1") (pin "1") (pinfunction "1_1") (pintype "bidirectional"))
      (node (ref "C3") (pin "1") (pinfunction "1_1") (pintype "passive"))
      (node (ref "R3") (pin "1") (pinfunction "1_1") (pintype "passive"))
    )
    (net (code "34") (name "Net-(B2-Pad1)") (class "Default")
      (node (ref "B2") (pin "1") (pinfunction "1_1") (pintype "bidirectional"))
      (node (ref "C4") (pin "1") (pinfunction "1_1") (pintype "passive"))
      (node (ref "R4") (pin "1") (pinfunction "1_1") (pintype "passive"))
    )
    (net (code "35") (name "Net-(B3-Pad1)") (class "Default")
      (node (ref "B3") (pin "1") (pinfunction "1_1") (pintype "bidirectional"))
      (node (ref "C5") (pin "1") (pinfunction "1_1") (pintype "passive"))
      (node (ref "R13") (pin "1") (pinfunction "1_1") (pintype "passive"))
    )
    (net (code "36") (name "Net-(B4-Pad1)") (class "Default")
      (node (ref "B4") (pin "1") (pinfunction "1_1") (pintype "bidirectional"))
      (node (ref "C6") (pin "1") (pinfunction "1_1") (pintype "passive"))
      (node (ref "R14") (pin "1") (pinfunction "1_1") (pintype "passive"))
    )
    (net (code "37") (name "Net-(LD1-C)") (class "Default")
      (node (ref "LD1") (pin "1") (pinfunction "C_1") (pintype "passive"))
      (node (ref "R5") (pin "1") (pinfunction "1_1") (pintype "passive"))
    )
    (net (code "38") (name "Net-(LD2-C)") (class "Default")
      (node (ref "LD2") (pin "1") (pinfunction "C_1") (pintype "passive"))
      (node (ref "R6") (pin "1") (pinfunction "1_1") (pintype "passive"))
    )
    (net (code "39") (name "Net-(LD3-C)") (class "Default")
      (node (ref "LD3") (pin "1") (pinfunction "C_1") (pintype "passive"))
      (node (ref "R7") (pin "1") (pinfunction "1_1") (pintype "passive"))
    )
    (net (code "40") (name "Net-(LD4-C)") (class "Default")
      (node (ref "LD4") (pin "1") (pinfunction "C_1") (pintype "passive"))
      (node (ref "R8") (pin "1") (pinfunction "1_1") (pintype "passive"))
    )
    (net (code "41") (name "Net-(LD5-C)") (class "Default")
      (node (ref "LD5") (pin "1") (pinfunction "C_1") (pintype "passive"))
      (node (ref "R9") (pin "1") (pinfunction "1_1") (pintype "passive"))
    )
    (net (code "42") (name "Net-(LD6-C)") (class "Default")
      (node (ref "LD6") (pin "1") (pinfunction "C_1") (pintype "passive"))
      (node (ref "R10") (pin "1") (pinfunction "1_1") (pintype "passive"))
    )
    (net (code "43") (name "Net-(LD7-C)") (class "Default")
      (node (ref "LD7") (pin "1") (pinfunction "C_1") (pintype "passive"))
      (node (ref "R11") (pin "1") (pinfunction "1_1") (pintype "passive"))
    )
    (net (code "44") (name "Net-(LD8-C)") (class "Default")
      (node (ref "LD8") (pin "1") (pinfunction "C_1") (pintype "passive"))
      (node (ref "R12") (pin "1") (pinfunction "1_1") (pintype "passive"))
    )
    (net (code "45") (name "Net-(R1-Pad1)") (class "Default")
      (node (ref "R1") (pin "1") (pinfunction "1_1") (pintype "passive"))
      (node (ref "SW1") (pin "1") (pinfunction "1_1") (pintype "bidirectional"))
    )
    (net (code "46") (name "Net-(R2-Pad1)") (class "Default")
      (node (ref "R2") (pin "1") (pinfunction "1_1") (pintype "passive"))
      (node (ref "SW1") (pin "2") (pinfunction "2_2") (pintype "bidirectional"))
    )
    (net (code "47") (name "P3V3") (class "Default")
      (node (ref "C1") (pin "2") (pinfunction "2_2") (pintype "passive"))
      (node (ref "C2") (pin "2") (pinfunction "2_2") (pintype "passive"))
      (node (ref "IC1") (pin "16") (pinfunction "VCC_16") (pintype "power_in"))
      (node (ref "J17") (pin "A10") (pinfunction "A10_A10") (pintype "bidirectional"))
    )
    (net (code "48") (name "unconnected-(IC1-QS1-Pad9)") (class "Default")
      (node (ref "IC1") (pin "9") (pinfunction "QS1_9") (pintype "output"))
    )
    (net (code "49") (name "unconnected-(IC1-QS2-Pad10)") (class "Default")
      (node (ref "IC1") (pin "10") (pinfunction "QS2_10") (pintype "output"))
    )
    (net (code "50") (name "unconnected-(Standoff1-Pad1)") (class "Default")
      (node (ref "Standoff1") (pin "1") (pinfunction "1_1") (pintype "bidirectional"))
    )
    (net (code "51") (name "unconnected-(Standoff2-Pad1)") (class "Default")
      (node (ref "Standoff2") (pin "1") (pinfunction "1_1") (pintype "bidirectional"))
    )
    (net (code "52") (name "unconnected-(Standoff3-Pad1)") (class "Default")
      (node (ref "Standoff3") (pin "1") (pinfunction "1_1") (pintype "bidirectional"))
    )
    (net (code "53") (name "unconnected-(Standoff4-Pad1)") (class "Default")
      (node (ref "Standoff4") (pin "1") (pinfunction "1_1") (pintype "bidirectional"))
    )
  )
)
